# 14-Counter74LS192.net
KiCad netlist of a schematic drawn in Altium Designer
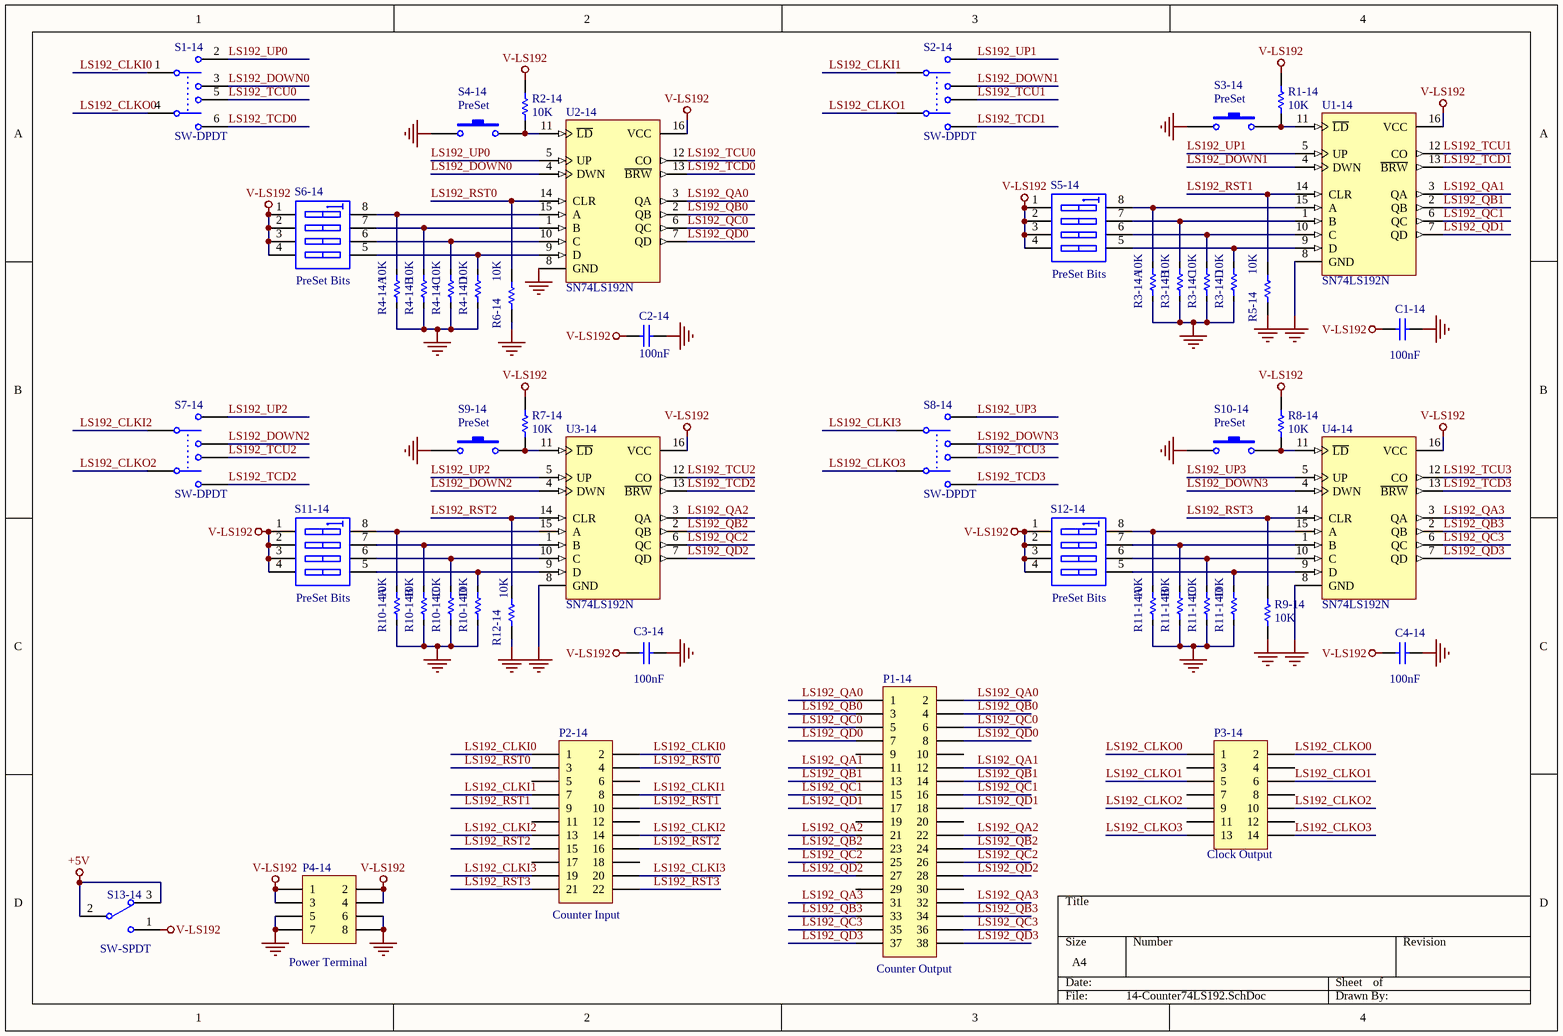
[diagram p0: 14-Counter74LS192.SchDoc]

(export (version "E")
  (design (tool "Eeschema 10.0.6"))
  (components
    (comp (ref "C1-14")
      (value "100nF")
      (footprint "c-0805")
      (description "Capacitor")
      (fields (field (name "Comment") "104") (field (name "PUBLISHER") "Altium Limited"))
      (libsource (lib "Miscellaneous Devices") (part "Cap"))
    )
    (comp (ref "C2-14")
      (value "100nF")
      (footprint "c-0805")
      (description "Capacitor")
      (fields (field (name "Comment") "104") (field (name "PUBLISHER") "Altium Limited"))
      (libsource (lib "Miscellaneous Devices") (part "Cap"))
    )
    (comp (ref "C3-14")
      (value "100nF")
      (footprint "c-0805")
      (description "Capacitor")
      (fields (field (name "Comment") "104") (field (name "PUBLISHER") "Altium Limited"))
      (libsource (lib "Miscellaneous Devices") (part "Cap"))
    )
    (comp (ref "C4-14")
      (value "100nF")
      (footprint "c-0805")
      (description "Capacitor")
      (fields (field (name "Comment") "104") (field (name "PUBLISHER") "Altium Limited"))
      (libsource (lib "Miscellaneous Devices") (part "Cap"))
    )
    (comp (ref "P1-14")
      (value "Counter Output")
      (footprint "JP2.54-F-2x19A")
      (description "Header, 19-Pin, Dual row")
      (fields (field (name "Comment") "Header 19X2"))
      (libsource (lib "Miscellaneous Connectors") (part "Header 19X2"))
    )
    (comp (ref "P2-14")
      (value "Counter Input")
      (footprint "JP2.54-F-2x11A")
      (description "Header, 11-Pin, Dual row")
      (fields (field (name "Comment") "Header 11X2"))
      (libsource (lib "Miscellaneous Connectors") (part "Header 11X2"))
    )
    (comp (ref "P3-14")
      (value "Clock Output")
      (footprint "JP2.54-F-2x07A")
      (description "Header, 7-Pin, Dual row")
      (fields (field (name "Comment") "Header 7X2"))
      (libsource (lib "Miscellaneous Connectors") (part "Header 7X2"))
    )
    (comp (ref "P4-14")
      (value "Header 4X2")
      (footprint "JP2.54-F-2x04A")
      (description "Header, 4-Pin, Dual row")
      (fields (field (name "PUBLISHER") "Power Terminal"))
      (libsource (lib "Miscellaneous Connectors") (part "Header 4X2"))
    )
    (comp (ref "R1-14")
      (value "10K")
      (footprint "R-0805")
      (description "Resistor")
      (fields (field (name "PUBLISHER") "Altium Limited"))
      (libsource (lib "Miscellaneous Devices") (part "Res1"))
    )
    (comp (ref "R2-14")
      (value "10K")
      (footprint "R-0805")
      (description "Resistor")
      (fields (field (name "PUBLISHER") "Altium Limited"))
      (libsource (lib "Miscellaneous Devices") (part "Res1"))
    )
    (comp (ref "R3-14")
      (value "10K")
      (footprint "R-Array-0603-4")
      (description "RES ARRAY 4 RES 330 OHM 1206")
      (fields
        (field (name "DIGI-KEY PART NUMBER") "Y9331TR-ND")
        (field (name "MANUFACTURER") "Panasonic Electronic Components")
      )
      (libsource (lib "Dlib") (part "R-8P4R"))
    )
    (comp (ref "R4-14")
      (value "10K")
      (footprint "R-Array-0603-4")
      (description "RES ARRAY 4 RES 330 OHM 1206")
      (fields
        (field (name "DIGI-KEY PART NUMBER") "Y9331TR-ND")
        (field (name "MANUFACTURER") "Panasonic Electronic Components")
      )
      (libsource (lib "Dlib") (part "R-8P4R"))
    )
    (comp (ref "R5-14")
      (value "10K")
      (footprint "R-0805")
      (description "Resistor")
      (fields (field (name "PUBLISHER") "Altium Limited"))
      (libsource (lib "Miscellaneous Devices") (part "Res1"))
    )
    (comp (ref "R6-14")
      (value "10K")
      (footprint "R-0805")
      (description "Resistor")
      (fields (field (name "PUBLISHER") "Altium Limited"))
      (libsource (lib "Miscellaneous Devices") (part "Res1"))
    )
    (comp (ref "R7-14")
      (value "10K")
      (footprint "R-0805")
      (description "Resistor")
      (fields (field (name "PUBLISHER") "Altium Limited"))
      (libsource (lib "Miscellaneous Devices") (part "Res1"))
    )
    (comp (ref "R8-14")
      (value "10K")
      (footprint "R-0805")
      (description "Resistor")
      (fields (field (name "PUBLISHER") "Altium Limited"))
      (libsource (lib "Miscellaneous Devices") (part "Res1"))
    )
    (comp (ref "R9-14")
      (value "10K")
      (footprint "R-0805")
      (description "Resistor")
      (fields (field (name "PUBLISHER") "Altium Limited"))
      (libsource (lib "Miscellaneous Devices") (part "Res1"))
    )
    (comp (ref "R10-14")
      (value "10K")
      (footprint "R-Array-0603-4")
      (description "RES ARRAY 4 RES 330 OHM 1206")
      (fields
        (field (name "DIGI-KEY PART NUMBER") "Y9331TR-ND")
        (field (name "MANUFACTURER") "Panasonic Electronic Components")
      )
      (libsource (lib "Dlib") (part "R-8P4R"))
    )
    (comp (ref "R11-14")
      (value "10K")
      (footprint "R-Array-0603-4")
      (description "RES ARRAY 4 RES 330 OHM 1206")
      (fields
        (field (name "DIGI-KEY PART NUMBER") "Y9331TR-ND")
        (field (name "MANUFACTURER") "Panasonic Electronic Components")
      )
      (libsource (lib "Dlib") (part "R-8P4R"))
    )
    (comp (ref "R12-14")
      (value "10K")
      (footprint "R-0805")
      (description "Resistor")
      (fields (field (name "PUBLISHER") "Altium Limited"))
      (libsource (lib "Miscellaneous Devices") (part "Res1"))
    )
    (comp (ref "S1-14")
      (value "SW-DPDT")
      (footprint "DPDT-6")
      (description "Double-Pole, Double-Throw Switch")
      (fields (field (name "PUBLISHER") "Altium Limited"))
      (libsource (lib "") (part "SW-DPDT_1"))
    )
    (comp (ref "S2-14")
      (value "SW-DPDT")
      (footprint "DPDT-6")
      (description "Double-Pole, Double-Throw Switch")
      (fields (field (name "PUBLISHER") "Altium Limited"))
      (libsource (lib "Miscellaneous Devices") (part "SW-DPDT"))
    )
    (comp (ref "S3-14")
      (value "PreSet")
      (footprint "SW-T-S6-SMD")
      (description "Switch")
      (fields (field (name "Comment") "SW-S6"))
      (libsource (lib "Miscellaneous Devices") (part "SW-PB"))
    )
    (comp (ref "S4-14")
      (value "PreSet")
      (footprint "SW-T-S6-SMD")
      (description "Switch")
      (fields (field (name "Comment") "SW-S6"))
      (libsource (lib "Miscellaneous Devices") (part "SW-PB"))
    )
    (comp (ref "S5-14")
      (value "PreSet Bits")
      (footprint "SW-DIP4-SMD")
      (description "DIP Switch, 4 Position, SPST")
      (fields (field (name "Comment") "SW DIP-4"))
      (libsource (lib "Miscellaneous Devices") (part "SW DIP-4"))
    )
    (comp (ref "S6-14")
      (value "PreSet Bits")
      (footprint "SW-DIP4-SMD")
      (description "DIP Switch, 4 Position, SPST")
      (fields (field (name "Comment") "SW DIP-4"))
      (libsource (lib "Miscellaneous Devices") (part "SW DIP-4"))
    )
    (comp (ref "S7-14")
      (value "SW-DPDT")
      (footprint "DPDT-6")
      (description "Double-Pole, Double-Throw Switch")
      (fields (field (name "PUBLISHER") "Altium Limited"))
      (libsource (lib "Miscellaneous Devices") (part "SW-DPDT"))
    )
    (comp (ref "S8-14")
      (value "SW-DPDT")
      (footprint "DPDT-6")
      (description "Double-Pole, Double-Throw Switch")
      (fields (field (name "PUBLISHER") "Altium Limited"))
      (libsource (lib "Miscellaneous Devices") (part "SW-DPDT"))
    )
    (comp (ref "S9-14")
      (value "PreSet")
      (footprint "SW-T-S6-SMD")
      (description "Switch")
      (fields (field (name "Comment") "SW-S6"))
      (libsource (lib "Miscellaneous Devices") (part "SW-PB"))
    )
    (comp (ref "S10-14")
      (value "PreSet")
      (footprint "SW-T-S6-SMD")
      (description "Switch")
      (fields (field (name "Comment") "SW-S6"))
      (libsource (lib "Miscellaneous Devices") (part "SW-PB"))
    )
    (comp (ref "S11-14")
      (value "PreSet Bits")
      (footprint "SW-DIP4-SMD")
      (description "DIP Switch, 4 Position, SPST")
      (fields (field (name "Comment") "SW DIP-4"))
      (libsource (lib "Miscellaneous Devices") (part "SW DIP-4"))
    )
    (comp (ref "S12-14")
      (value "PreSet Bits")
      (footprint "SW-DIP4-SMD")
      (description "DIP Switch, 4 Position, SPST")
      (fields (field (name "Comment") "SW DIP-4"))
      (libsource (lib "Miscellaneous Devices") (part "SW DIP-4"))
    )
    (comp (ref "S13-14")
      (value "SW-SPDT")
      (footprint "SW-SLIDE-2P-2W")
      (description "SPDT Subminiature Toggle Switch, Right Angle Mounting, Vertical Actuation")
      (fields (field (name "PUBLISHER") "Altium Limited"))
      (libsource (lib "Miscellaneous Devices") (part "SW-SPDT"))
    )
    (comp (ref "U1-14")
      (value "SN74LS192N")
      (footprint "SK-DIP16-300")
      (description "Synchronous 4-Bit Up/Down Counter (Dual Clock with Clear)")
      (fields (field (name "PUBLISHER") "Altium Limited"))
      (libsource (lib "TI Logic Counter") (part "SN74LS192N"))
    )
    (comp (ref "U2-14")
      (value "SN74LS192N")
      (footprint "SK-DIP16-300")
      (description "Synchronous 4-Bit Up/Down Counter (Dual Clock with Clear)")
      (fields (field (name "PUBLISHER") "Altium Limited"))
      (libsource (lib "TI Logic Counter") (part "SN74LS192N"))
    )
    (comp (ref "U3-14")
      (value "SN74LS192N")
      (footprint "SK-DIP16-300")
      (description "Synchronous 4-Bit Up/Down Counter (Dual Clock with Clear)")
      (fields (field (name "PUBLISHER") "Altium Limited"))
      (libsource (lib "TI Logic Counter") (part "SN74LS192N"))
    )
    (comp (ref "U4-14")
      (value "SN74LS192N")
      (footprint "SK-DIP16-300")
      (description "Synchronous 4-Bit Up/Down Counter (Dual Clock with Clear)")
      (fields (field (name "PUBLISHER") "Altium Limited"))
      (libsource (lib "TI Logic Counter") (part "SN74LS192N"))
    )
  )
  (nets
    (net (code "1") (name "+5V") (class "Default")
      (node (ref "S13-14") (pin "2") (pinfunction "2_2") (pintype "passive"))
      (node (ref "S13-14") (pin "3") (pinfunction "3_3") (pintype "passive"))
    )
    (net (code "2") (name "/LS192_CLKI0") (class "Default")
      (node (ref "P2-14") (pin "1") (pinfunction "1_1") (pintype "passive"))
      (node (ref "P2-14") (pin "2") (pinfunction "2_2") (pintype "passive"))
      (node (ref "S1-14") (pin "1") (pinfunction "1_1") (pintype "passive"))
    )
    (net (code "3") (name "/LS192_CLKI1") (class "Default")
      (node (ref "P2-14") (pin "7") (pinfunction "7_7") (pintype "passive"))
      (node (ref "P2-14") (pin "8") (pinfunction "8_8") (pintype "passive"))
      (node (ref "S2-14") (pin "1") (pinfunction "1_1") (pintype "passive"))
    )
    (net (code "4") (name "/LS192_CLKI2") (class "Default")
      (node (ref "P2-14") (pin "13") (pinfunction "13_13") (pintype "passive"))
      (node (ref "P2-14") (pin "14") (pinfunction "14_14") (pintype "passive"))
      (node (ref "S7-14") (pin "1") (pinfunction "1_1") (pintype "passive"))
    )
    (net (code "5") (name "/LS192_CLKI3") (class "Default")
      (node (ref "P2-14") (pin "19") (pinfunction "19_19") (pintype "passive"))
      (node (ref "P2-14") (pin "20") (pinfunction "20_20") (pintype "passive"))
      (node (ref "S8-14") (pin "1") (pinfunction "1_1") (pintype "passive"))
    )
    (net (code "6") (name "/LS192_CLKO0") (class "Default")
      (node (ref "P3-14") (pin "1") (pinfunction "1_1") (pintype "passive"))
      (node (ref "P3-14") (pin "2") (pinfunction "2_2") (pintype "passive"))
      (node (ref "S1-14") (pin "4") (pinfunction "4_4") (pintype "passive"))
    )
    (net (code "7") (name "/LS192_CLKO1") (class "Default")
      (node (ref "P3-14") (pin "5") (pinfunction "5_5") (pintype "passive"))
      (node (ref "P3-14") (pin "6") (pinfunction "6_6") (pintype "passive"))
      (node (ref "S2-14") (pin "4") (pinfunction "4_4") (pintype "passive"))
    )
    (net (code "8") (name "/LS192_CLKO2") (class "Default")
      (node (ref "P3-14") (pin "10") (pinfunction "10_10") (pintype "passive"))
      (node (ref "P3-14") (pin "9") (pinfunction "9_9") (pintype "passive"))
      (node (ref "S7-14") (pin "4") (pinfunction "4_4") (pintype "passive"))
    )
    (net (code "9") (name "/LS192_CLKO3") (class "Default")
      (node (ref "P3-14") (pin "13") (pinfunction "13_13") (pintype "passive"))
      (node (ref "P3-14") (pin "14") (pinfunction "14_14") (pintype "passive"))
      (node (ref "S8-14") (pin "4") (pinfunction "4_4") (pintype "passive"))
    )
    (net (code "10") (name "/LS192_DOWN0") (class "Default")
      (node (ref "S1-14") (pin "3") (pinfunction "3_3") (pintype "passive"))
      (node (ref "U2-14") (pin "4") (pinfunction "DWN_4") (pintype "input"))
    )
    (net (code "11") (name "/LS192_DOWN1") (class "Default")
      (node (ref "S2-14") (pin "3") (pinfunction "3_3") (pintype "passive"))
      (node (ref "U1-14") (pin "4") (pinfunction "DWN_4") (pintype "input"))
    )
    (net (code "12") (name "/LS192_DOWN2") (class "Default")
      (node (ref "S7-14") (pin "3") (pinfunction "3_3") (pintype "passive"))
      (node (ref "U3-14") (pin "4") (pinfunction "DWN_4") (pintype "input"))
    )
    (net (code "13") (name "/LS192_DOWN3") (class "Default")
      (node (ref "S8-14") (pin "3") (pinfunction "3_3") (pintype "passive"))
      (node (ref "U4-14") (pin "4") (pinfunction "DWN_4") (pintype "input"))
    )
    (net (code "14") (name "/LS192_QA0") (class "Default")
      (node (ref "P1-14") (pin "1") (pinfunction "1_1") (pintype "passive"))
      (node (ref "P1-14") (pin "2") (pinfunction "2_2") (pintype "passive"))
      (node (ref "U2-14") (pin "3") (pinfunction "QA_3") (pintype "output"))
    )
    (net (code "15") (name "/LS192_QA1") (class "Default")
      (node (ref "P1-14") (pin "11") (pinfunction "11_11") (pintype "passive"))
      (node (ref "P1-14") (pin "12") (pinfunction "12_12") (pintype "passive"))
      (node (ref "U1-14") (pin "3") (pinfunction "QA_3") (pintype "output"))
    )
    (net (code "16") (name "/LS192_QA2") (class "Default")
      (node (ref "P1-14") (pin "21") (pinfunction "21_21") (pintype "passive"))
      (node (ref "P1-14") (pin "22") (pinfunction "22_22") (pintype "passive"))
      (node (ref "U3-14") (pin "3") (pinfunction "QA_3") (pintype "output"))
    )
    (net (code "17") (name "/LS192_QA3") (class "Default")
      (node (ref "P1-14") (pin "31") (pinfunction "31_31") (pintype "passive"))
      (node (ref "P1-14") (pin "32") (pinfunction "32_32") (pintype "passive"))
      (node (ref "U4-14") (pin "3") (pinfunction "QA_3") (pintype "output"))
    )
    (net (code "18") (name "/LS192_QB0") (class "Default")
      (node (ref "P1-14") (pin "3") (pinfunction "3_3") (pintype "passive"))
      (node (ref "P1-14") (pin "4") (pinfunction "4_4") (pintype "passive"))
      (node (ref "U2-14") (pin "2") (pinfunction "QB_2") (pintype "output"))
    )
    (net (code "19") (name "/LS192_QB1") (class "Default")
      (node (ref "P1-14") (pin "13") (pinfunction "13_13") (pintype "passive"))
      (node (ref "P1-14") (pin "14") (pinfunction "14_14") (pintype "passive"))
      (node (ref "U1-14") (pin "2") (pinfunction "QB_2") (pintype "output"))
    )
    (net (code "20") (name "/LS192_QB2") (class "Default")
      (node (ref "P1-14") (pin "23") (pinfunction "23_23") (pintype "passive"))
      (node (ref "P1-14") (pin "24") (pinfunction "24_24") (pintype "passive"))
      (node (ref "U3-14") (pin "2") (pinfunction "QB_2") (pintype "output"))
    )
    (net (code "21") (name "/LS192_QB3") (class "Default")
      (node (ref "P1-14") (pin "33") (pinfunction "33_33") (pintype "passive"))
      (node (ref "P1-14") (pin "34") (pinfunction "34_34") (pintype "passive"))
      (node (ref "U4-14") (pin "2") (pinfunction "QB_2") (pintype "output"))
    )
    (net (code "22") (name "/LS192_QC0") (class "Default")
      (node (ref "P1-14") (pin "5") (pinfunction "5_5") (pintype "passive"))
      (node (ref "P1-14") (pin "6") (pinfunction "6_6") (pintype "passive"))
      (node (ref "U2-14") (pin "6") (pinfunction "QC_6") (pintype "output"))
    )
    (net (code "23") (name "/LS192_QC1") (class "Default")
      (node (ref "P1-14") (pin "15") (pinfunction "15_15") (pintype "passive"))
      (node (ref "P1-14") (pin "16") (pinfunction "16_16") (pintype "passive"))
      (node (ref "U1-14") (pin "6") (pinfunction "QC_6") (pintype "output"))
    )
    (net (code "24") (name "/LS192_QC2") (class "Default")
      (node (ref "P1-14") (pin "25") (pinfunction "25_25") (pintype "passive"))
      (node (ref "P1-14") (pin "26") (pinfunction "26_26") (pintype "passive"))
      (node (ref "U3-14") (pin "6") (pinfunction "QC_6") (pintype "output"))
    )
    (net (code "25") (name "/LS192_QC3") (class "Default")
      (node (ref "P1-14") (pin "35") (pinfunction "35_35") (pintype "passive"))
      (node (ref "P1-14") (pin "36") (pinfunction "36_36") (pintype "passive"))
      (node (ref "U4-14") (pin "6") (pinfunction "QC_6") (pintype "output"))
    )
    (net (code "26") (name "/LS192_QD0") (class "Default")
      (node (ref "P1-14") (pin "7") (pinfunction "7_7") (pintype "passive"))
      (node (ref "P1-14") (pin "8") (pinfunction "8_8") (pintype "passive"))
      (node (ref "U2-14") (pin "7") (pinfunction "QD_7") (pintype "output"))
    )
    (net (code "27") (name "/LS192_QD1") (class "Default")
      (node (ref "P1-14") (pin "17") (pinfunction "17_17") (pintype "passive"))
      (node (ref "P1-14") (pin "18") (pinfunction "18_18") (pintype "passive"))
      (node (ref "U1-14") (pin "7") (pinfunction "QD_7") (pintype "output"))
    )
    (net (code "28") (name "/LS192_QD2") (class "Default")
      (node (ref "P1-14") (pin "27") (pinfunction "27_27") (pintype "passive"))
      (node (ref "P1-14") (pin "28") (pinfunction "28_28") (pintype "passive"))
      (node (ref "U3-14") (pin "7") (pinfunction "QD_7") (pintype "output"))
    )
    (net (code "29") (name "/LS192_QD3") (class "Default")
      (node (ref "P1-14") (pin "37") (pinfunction "37_37") (pintype "passive"))
      (node (ref "P1-14") (pin "38") (pinfunction "38_38") (pintype "passive"))
      (node (ref "U4-14") (pin "7") (pinfunction "QD_7") (pintype "output"))
    )
    (net (code "30") (name "/LS192_RST0") (class "Default")
      (node (ref "P2-14") (pin "3") (pinfunction "3_3") (pintype "passive"))
      (node (ref "P2-14") (pin "4") (pinfunction "4_4") (pintype "passive"))
      (node (ref "R6-14") (pin "2") (pinfunction "2_2") (pintype "passive"))
      (node (ref "U2-14") (pin "14") (pinfunction "CLR_14") (pintype "input"))
    )
    (net (code "31") (name "/LS192_RST1") (class "Default")
      (node (ref "P2-14") (pin "10") (pinfunction "10_10") (pintype "passive"))
      (node (ref "P2-14") (pin "9") (pinfunction "9_9") (pintype "passive"))
      (node (ref "R5-14") (pin "2") (pinfunction "2_2") (pintype "passive"))
      (node (ref "U1-14") (pin "14") (pinfunction "CLR_14") (pintype "input"))
    )
    (net (code "32") (name "/LS192_RST2") (class "Default")
      (node (ref "P2-14") (pin "15") (pinfunction "15_15") (pintype "passive"))
      (node (ref "P2-14") (pin "16") (pinfunction "16_16") (pintype "passive"))
      (node (ref "R12-14") (pin "2") (pinfunction "2_2") (pintype "passive"))
      (node (ref "U3-14") (pin "14") (pinfunction "CLR_14") (pintype "input"))
    )
    (net (code "33") (name "/LS192_RST3") (class "Default")
      (node (ref "P2-14") (pin "21") (pinfunction "21_21") (pintype "passive"))
      (node (ref "P2-14") (pin "22") (pinfunction "22_22") (pintype "passive"))
      (node (ref "R9-14") (pin "2") (pinfunction "2_2") (pintype "passive"))
      (node (ref "U4-14") (pin "14") (pinfunction "CLR_14") (pintype "input"))
    )
    (net (code "34") (name "/LS192_TCD0") (class "Default")
      (node (ref "S1-14") (pin "6") (pinfunction "6_6") (pintype "passive"))
      (node (ref "U2-14") (pin "13") (pinfunction "~{BRW}_13") (pintype "output"))
    )
    (net (code "35") (name "/LS192_TCD1") (class "Default")
      (node (ref "S2-14") (pin "6") (pinfunction "6_6") (pintype "passive"))
      (node (ref "U1-14") (pin "13") (pinfunction "~{BRW}_13") (pintype "output"))
    )
    (net (code "36") (name "/LS192_TCD2") (class "Default")
      (node (ref "S7-14") (pin "6") (pinfunction "6_6") (pintype "passive"))
      (node (ref "U3-14") (pin "13") (pinfunction "~{BRW}_13") (pintype "output"))
    )
    (net (code "37") (name "/LS192_TCD3") (class "Default")
      (node (ref "S8-14") (pin "6") (pinfunction "6_6") (pintype "passive"))
      (node (ref "U4-14") (pin "13") (pinfunction "~{BRW}_13") (pintype "output"))
    )
    (net (code "38") (name "/LS192_TCU0") (class "Default")
      (node (ref "S1-14") (pin "5") (pinfunction "5_5") (pintype "passive"))
      (node (ref "U2-14") (pin "12") (pinfunction "CO_12") (pintype "output"))
    )
    (net (code "39") (name "/LS192_TCU1") (class "Default")
      (node (ref "S2-14") (pin "5") (pinfunction "5_5") (pintype "passive"))
      (node (ref "U1-14") (pin "12") (pinfunction "CO_12") (pintype "output"))
    )
    (net (code "40") (name "/LS192_TCU2") (class "Default")
      (node (ref "S7-14") (pin "5") (pinfunction "5_5") (pintype "passive"))
      (node (ref "U3-14") (pin "12") (pinfunction "CO_12") (pintype "output"))
    )
    (net (code "41") (name "/LS192_TCU3") (class "Default")
      (node (ref "S8-14") (pin "5") (pinfunction "5_5") (pintype "passive"))
      (node (ref "U4-14") (pin "12") (pinfunction "CO_12") (pintype "output"))
    )
    (net (code "42") (name "/LS192_UP0") (class "Default")
      (node (ref "S1-14") (pin "2") (pinfunction "2_2") (pintype "passive"))
      (node (ref "U2-14") (pin "5") (pinfunction "UP_5") (pintype "input"))
    )
    (net (code "43") (name "/LS192_UP1") (class "Default")
      (node (ref "S2-14") (pin "2") (pinfunction "2_2") (pintype "passive"))
      (node (ref "U1-14") (pin "5") (pinfunction "UP_5") (pintype "input"))
    )
    (net (code "44") (name "/LS192_UP2") (class "Default")
      (node (ref "S7-14") (pin "2") (pinfunction "2_2") (pintype "passive"))
      (node (ref "U3-14") (pin "5") (pinfunction "UP_5") (pintype "input"))
    )
    (net (code "45") (name "/LS192_UP3") (class "Default")
      (node (ref "S8-14") (pin "2") (pinfunction "2_2") (pintype "passive"))
      (node (ref "U4-14") (pin "5") (pinfunction "UP_5") (pintype "input"))
    )
    (net (code "46") (name "GND") (class "Default")
      (node (ref "C1-14") (pin "2") (pinfunction "2_2") (pintype "passive"))
      (node (ref "C2-14") (pin "2") (pinfunction "2_2") (pintype "passive"))
      (node (ref "C3-14") (pin "2") (pinfunction "2_2") (pintype "passive"))
      (node (ref "C4-14") (pin "2") (pinfunction "2_2") (pintype "passive"))
      (node (ref "P4-14") (pin "5") (pinfunction "5_5") (pintype "passive"))
      (node (ref "P4-14") (pin "6") (pinfunction "6_6") (pintype "passive"))
      (node (ref "P4-14") (pin "7") (pinfunction "7_7") (pintype "passive"))
      (node (ref "P4-14") (pin "8") (pinfunction "8_8") (pintype "passive"))
      (node (ref "R10-14") (pin "1") (pinfunction "1_1") (pintype "passive"))
      (node (ref "R10-14") (pin "3") (pinfunction "1_3") (pintype "passive"))
      (node (ref "R10-14") (pin "5") (pinfunction "1_5") (pintype "passive"))
      (node (ref "R10-14") (pin "7") (pinfunction "1_7") (pintype "passive"))
      (node (ref "R11-14") (pin "1") (pinfunction "1_1") (pintype "passive"))
      (node (ref "R11-14") (pin "3") (pinfunction "1_3") (pintype "passive"))
      (node (ref "R11-14") (pin "5") (pinfunction "1_5") (pintype "passive"))
      (node (ref "R11-14") (pin "7") (pinfunction "1_7") (pintype "passive"))
      (node (ref "R12-14") (pin "1") (pinfunction "1_1") (pintype "passive"))
      (node (ref "R3-14") (pin "1") (pinfunction "1_1") (pintype "passive"))
      (node (ref "R3-14") (pin "3") (pinfunction "1_3") (pintype "passive"))
      (node (ref "R3-14") (pin "5") (pinfunction "1_5") (pintype "passive"))
      (node (ref "R3-14") (pin "7") (pinfunction "1_7") (pintype "passive"))
      (node (ref "R4-14") (pin "1") (pinfunction "1_1") (pintype "passive"))
      (node (ref "R4-14") (pin "3") (pinfunction "1_3") (pintype "passive"))
      (node (ref "R4-14") (pin "5") (pinfunction "1_5") (pintype "passive"))
      (node (ref "R4-14") (pin "7") (pinfunction "1_7") (pintype "passive"))
      (node (ref "R5-14") (pin "1") (pinfunction "1_1") (pintype "passive"))
      (node (ref "R6-14") (pin "1") (pinfunction "1_1") (pintype "passive"))
      (node (ref "R9-14") (pin "1") (pinfunction "1_1") (pintype "passive"))
      (node (ref "S10-14") (pin "1") (pinfunction "1_1") (pintype "passive"))
      (node (ref "S3-14") (pin "1") (pinfunction "1_1") (pintype "passive"))
      (node (ref "S4-14") (pin "1") (pinfunction "1_1") (pintype "passive"))
      (node (ref "S9-14") (pin "1") (pinfunction "1_1") (pintype "passive"))
      (node (ref "U1-14") (pin "8") (pinfunction "GND_8") (pintype "power_in"))
      (node (ref "U2-14") (pin "8") (pinfunction "GND_8") (pintype "power_in"))
      (node (ref "U3-14") (pin "8") (pinfunction "GND_8") (pintype "power_in"))
      (node (ref "U4-14") (pin "8") (pinfunction "GND_8") (pintype "power_in"))
    )
    (net (code "47") (name "Net-(R3-14B-2)") (class "Default")
      (node (ref "R3-14") (pin "4") (pinfunction "2_4") (pintype "passive"))
      (node (ref "S5-14") (pin "7") (pinfunction "B2_7") (pintype "passive"))
      (node (ref "U1-14") (pin "1") (pinfunction "B_1") (pintype "input"))
    )
    (net (code "48") (name "Net-(R3-14C-2)") (class "Default")
      (node (ref "R3-14") (pin "6") (pinfunction "2_6") (pintype "passive"))
      (node (ref "S5-14") (pin "6") (pinfunction "B3_6") (pintype "passive"))
      (node (ref "U1-14") (pin "10") (pinfunction "C_10") (pintype "input"))
    )
    (net (code "49") (name "Net-(R3-14D-2)") (class "Default")
      (node (ref "R3-14") (pin "8") (pinfunction "2_8") (pintype "passive"))
      (node (ref "S5-14") (pin "5") (pinfunction "B4_5") (pintype "passive"))
      (node (ref "U1-14") (pin "9") (pinfunction "D_9") (pintype "input"))
    )
    (net (code "50") (name "Net-(R4-14B-2)") (class "Default")
      (node (ref "R4-14") (pin "4") (pinfunction "2_4") (pintype "passive"))
      (node (ref "S6-14") (pin "7") (pinfunction "B2_7") (pintype "passive"))
      (node (ref "U2-14") (pin "1") (pinfunction "B_1") (pintype "input"))
    )
    (net (code "51") (name "Net-(R4-14C-2)") (class "Default")
      (node (ref "R4-14") (pin "6") (pinfunction "2_6") (pintype "passive"))
      (node (ref "S6-14") (pin "6") (pinfunction "B3_6") (pintype "passive"))
      (node (ref "U2-14") (pin "10") (pinfunction "C_10") (pintype "input"))
    )
    (net (code "52") (name "Net-(R4-14D-2)") (class "Default")
      (node (ref "R4-14") (pin "8") (pinfunction "2_8") (pintype "passive"))
      (node (ref "S6-14") (pin "5") (pinfunction "B4_5") (pintype "passive"))
      (node (ref "U2-14") (pin "9") (pinfunction "D_9") (pintype "input"))
    )
    (net (code "53") (name "Net-(R10-14B-2)") (class "Default")
      (node (ref "R10-14") (pin "4") (pinfunction "2_4") (pintype "passive"))
      (node (ref "S11-14") (pin "7") (pinfunction "B2_7") (pintype "passive"))
      (node (ref "U3-14") (pin "1") (pinfunction "B_1") (pintype "input"))
    )
    (net (code "54") (name "Net-(R10-14C-2)") (class "Default")
      (node (ref "R10-14") (pin "6") (pinfunction "2_6") (pintype "passive"))
      (node (ref "S11-14") (pin "6") (pinfunction "B3_6") (pintype "passive"))
      (node (ref "U3-14") (pin "10") (pinfunction "C_10") (pintype "input"))
    )
    (net (code "55") (name "Net-(R10-14D-2)") (class "Default")
      (node (ref "R10-14") (pin "8") (pinfunction "2_8") (pintype "passive"))
      (node (ref "S11-14") (pin "5") (pinfunction "B4_5") (pintype "passive"))
      (node (ref "U3-14") (pin "9") (pinfunction "D_9") (pintype "input"))
    )
    (net (code "56") (name "Net-(R11-14B-2)") (class "Default")
      (node (ref "R11-14") (pin "4") (pinfunction "2_4") (pintype "passive"))
      (node (ref "S12-14") (pin "7") (pinfunction "B2_7") (pintype "passive"))
      (node (ref "U4-14") (pin "1") (pinfunction "B_1") (pintype "input"))
    )
    (net (code "57") (name "Net-(R11-14C-2)") (class "Default")
      (node (ref "R11-14") (pin "6") (pinfunction "2_6") (pintype "passive"))
      (node (ref "S12-14") (pin "6") (pinfunction "B3_6") (pintype "passive"))
      (node (ref "U4-14") (pin "10") (pinfunction "C_10") (pintype "input"))
    )
    (net (code "58") (name "Net-(R11-14D-2)") (class "Default")
      (node (ref "R11-14") (pin "8") (pinfunction "2_8") (pintype "passive"))
      (node (ref "S12-14") (pin "5") (pinfunction "B4_5") (pintype "passive"))
      (node (ref "U4-14") (pin "9") (pinfunction "D_9") (pintype "input"))
    )
    (net (code "59") (name "Net-(S5-14-B1)") (class "Default")
      (node (ref "R3-14") (pin "2") (pinfunction "2_2") (pintype "passive"))
      (node (ref "S5-14") (pin "8") (pinfunction "B1_8") (pintype "passive"))
      (node (ref "U1-14") (pin "15") (pinfunction "A_15") (pintype "input"))
    )
    (net (code "60") (name "Net-(S6-14-B1)") (class "Default")
      (node (ref "R4-14") (pin "2") (pinfunction "2_2") (pintype "passive"))
      (node (ref "S6-14") (pin "8") (pinfunction "B1_8") (pintype "passive"))
      (node (ref "U2-14") (pin "15") (pinfunction "A_15") (pintype "input"))
    )
    (net (code "61") (name "Net-(S11-14-B1)") (class "Default")
      (node (ref "R10-14") (pin "2") (pinfunction "2_2") (pintype "passive"))
      (node (ref "S11-14") (pin "8") (pinfunction "B1_8") (pintype "passive"))
      (node (ref "U3-14") (pin "15") (pinfunction "A_15") (pintype "input"))
    )
    (net (code "62") (name "Net-(S12-14-B1)") (class "Default")
      (node (ref "R11-14") (pin "2") (pinfunction "2_2") (pintype "passive"))
      (node (ref "S12-14") (pin "8") (pinfunction "B1_8") (pintype "passive"))
      (node (ref "U4-14") (pin "15") (pinfunction "A_15") (pintype "input"))
    )
    (net (code "63") (name "Net-(U1-14-~{LD})") (class "Default")
      (node (ref "R1-14") (pin "1") (pinfunction "1_1") (pintype "passive"))
      (node (ref "S3-14") (pin "2") (pinfunction "2_2") (pintype "passive"))
      (node (ref "U1-14") (pin "11") (pinfunction "~{LD}_11") (pintype "input"))
    )
    (net (code "64") (name "Net-(U2-14-~{LD})") (class "Default")
      (node (ref "R2-14") (pin "1") (pinfunction "1_1") (pintype "passive"))
      (node (ref "S4-14") (pin "2") (pinfunction "2_2") (pintype "passive"))
      (node (ref "U2-14") (pin "11") (pinfunction "~{LD}_11") (pintype "input"))
    )
    (net (code "65") (name "Net-(U3-14-~{LD})") (class "Default")
      (node (ref "R7-14") (pin "1") (pinfunction "1_1") (pintype "passive"))
      (node (ref "S9-14") (pin "2") (pinfunction "2_2") (pintype "passive"))
      (node (ref "U3-14") (pin "11") (pinfunction "~{LD}_11") (pintype "input"))
    )
    (net (code "66") (name "Net-(U4-14-~{LD})") (class "Default")
      (node (ref "R8-14") (pin "1") (pinfunction "1_1") (pintype "passive"))
      (node (ref "S10-14") (pin "2") (pinfunction "2_2") (pintype "passive"))
      (node (ref "U4-14") (pin "11") (pinfunction "~{LD}_11") (pintype "input"))
    )
    (net (code "67") (name "V-LS192") (class "Default")
      (node (ref "C1-14") (pin "1") (pinfunction "1_1") (pintype "passive"))
      (node (ref "C2-14") (pin "1") (pinfunction "1_1") (pintype "passive"))
      (node (ref "C3-14") (pin "1") (pinfunction "1_1") (pintype "passive"))
      (node (ref "C4-14") (pin "1") (pinfunction "1_1") (pintype "passive"))
      (node (ref "P4-14") (pin "1") (pinfunction "1_1") (pintype "passive"))
      (node (ref "P4-14") (pin "2") (pinfunction "2_2") (pintype "passive"))
      (node (ref "P4-14") (pin "3") (pinfunction "3_3") (pintype "passive"))
      (node (ref "P4-14") (pin "4") (pinfunction "4_4") (pintype "passive"))
      (node (ref "R1-14") (pin "2") (pinfunction "2_2") (pintype "passive"))
      (node (ref "R2-14") (pin "2") (pinfunction "2_2") (pintype "passive"))
      (node (ref "R7-14") (pin "2") (pinfunction "2_2") (pintype "passive"))
      (node (ref "R8-14") (pin "2") (pinfunction "2_2") (pintype "passive"))
      (node (ref "S11-14") (pin "1") (pinfunction "A1_1") (pintype "passive"))
      (node (ref "S11-14") (pin "2") (pinfunction "A2_2") (pintype "passive"))
      (node (ref "S11-14") (pin "3") (pinfunction "A3_3") (pintype "passive"))
      (node (ref "S11-14") (pin "4") (pinfunction "A4_4") (pintype "passive"))
      (node (ref "S12-14") (pin "1") (pinfunction "A1_1") (pintype "passive"))
      (node (ref "S12-14") (pin "2") (pinfunction "A2_2") (pintype "passive"))
      (node (ref "S12-14") (pin "3") (pinfunction "A3_3") (pintype "passive"))
      (node (ref "S12-14") (pin "4") (pinfunction "A4_4") (pintype "passive"))
      (node (ref "S13-14") (pin "1") (pinfunction "1_1") (pintype "passive"))
      (node (ref "S5-14") (pin "1") (pinfunction "A1_1") (pintype "passive"))
      (node (ref "S5-14") (pin "2") (pinfunction "A2_2") (pintype "passive"))
      (node (ref "S5-14") (pin "3") (pinfunction "A3_3") (pintype "passive"))
      (node (ref "S5-14") (pin "4") (pinfunction "A4_4") (pintype "passive"))
      (node (ref "S6-14") (pin "1") (pinfunction "A1_1") (pintype "passive"))
      (node (ref "S6-14") (pin "2") (pinfunction "A2_2") (pintype "passive"))
      (node (ref "S6-14") (pin "3") (pinfunction "A3_3") (pintype "passive"))
      (node (ref "S6-14") (pin "4") (pinfunction "A4_4") (pintype "passive"))
      (node (ref "U1-14") (pin "16") (pinfunction "VCC_16") (pintype "power_in"))
      (node (ref "U2-14") (pin "16") (pinfunction "VCC_16") (pintype "power_in"))
      (node (ref "U3-14") (pin "16") (pinfunction "VCC_16") (pintype "power_in"))
      (node (ref "U4-14") (pin "16") (pinfunction "VCC_16") (pintype "power_in"))
    )
    (net (code "68") (name "unconnected-(P1-14-Pad9)") (class "Default")
      (node (ref "P1-14") (pin "9") (pinfunction "9_9") (pintype "passive"))
    )
    (net (code "69") (name "unconnected-(P1-14-Pad10)") (class "Default")
      (node (ref "P1-14") (pin "10") (pinfunction "10_10") (pintype "passive"))
    )
    (net (code "70") (name "unconnected-(P1-14-Pad19)") (class "Default")
      (node (ref "P1-14") (pin "19") (pinfunction "19_19") (pintype "passive"))
    )
    (net (code "71") (name "unconnected-(P1-14-Pad20)") (class "Default")
      (node (ref "P1-14") (pin "20") (pinfunction "20_20") (pintype "passive"))
    )
    (net (code "72") (name "unconnected-(P1-14-Pad29)") (class "Default")
      (node (ref "P1-14") (pin "29") (pinfunction "29_29") (pintype "passive"))
    )
    (net (code "73") (name "unconnected-(P1-14-Pad30)") (class "Default")
      (node (ref "P1-14") (pin "30") (pinfunction "30_30") (pintype "passive"))
    )
    (net (code "74") (name "unconnected-(P2-14-Pad5)") (class "Default")
      (node (ref "P2-14") (pin "5") (pinfunction "5_5") (pintype "passive"))
    )
    (net (code "75") (name "unconnected-(P2-14-Pad6)") (class "Default")
      (node (ref "P2-14") (pin "6") (pinfunction "6_6") (pintype "passive"))
    )
    (net (code "76") (name "unconnected-(P2-14-Pad11)") (class "Default")
      (node (ref "P2-14") (pin "11") (pinfunction "11_11") (pintype "passive"))
    )
    (net (code "77") (name "unconnected-(P2-14-Pad12)") (class "Default")
      (node (ref "P2-14") (pin "12") (pinfunction "12_12") (pintype "passive"))
    )
    (net (code "78") (name "unconnected-(P2-14-Pad17)") (class "Default")
      (node (ref "P2-14") (pin "17") (pinfunction "17_17") (pintype "passive"))
    )
    (net (code "79") (name "unconnected-(P2-14-Pad18)") (class "Default")
      (node (ref "P2-14") (pin "18") (pinfunction "18_18") (pintype "passive"))
    )
    (net (code "80") (name "unconnected-(P3-14-Pad3)") (class "Default")
      (node (ref "P3-14") (pin "3") (pinfunction "3_3") (pintype "passive"))
    )
    (net (code "81") (name "unconnected-(P3-14-Pad4)") (class "Default")
      (node (ref "P3-14") (pin "4") (pinfunction "4_4") (pintype "passive"))
    )
    (net (code "82") (name "unconnected-(P3-14-Pad7)") (class "Default")
      (node (ref "P3-14") (pin "7") (pinfunction "7_7") (pintype "passive"))
    )
    (net (code "83") (name "unconnected-(P3-14-Pad8)") (class "Default")
      (node (ref "P3-14") (pin "8") (pinfunction "8_8") (pintype "passive"))
    )
    (net (code "84") (name "unconnected-(P3-14-Pad11)") (class "Default")
      (node (ref "P3-14") (pin "11") (pinfunction "11_11") (pintype "passive"))
    )
    (net (code "85") (name "unconnected-(P3-14-Pad12)") (class "Default")
      (node (ref "P3-14") (pin "12") (pinfunction "12_12") (pintype "passive"))
    )
  )
)
